# 7_3PCB_Sheet.net
KiCad netlist of a schematic drawn in EasyEDA
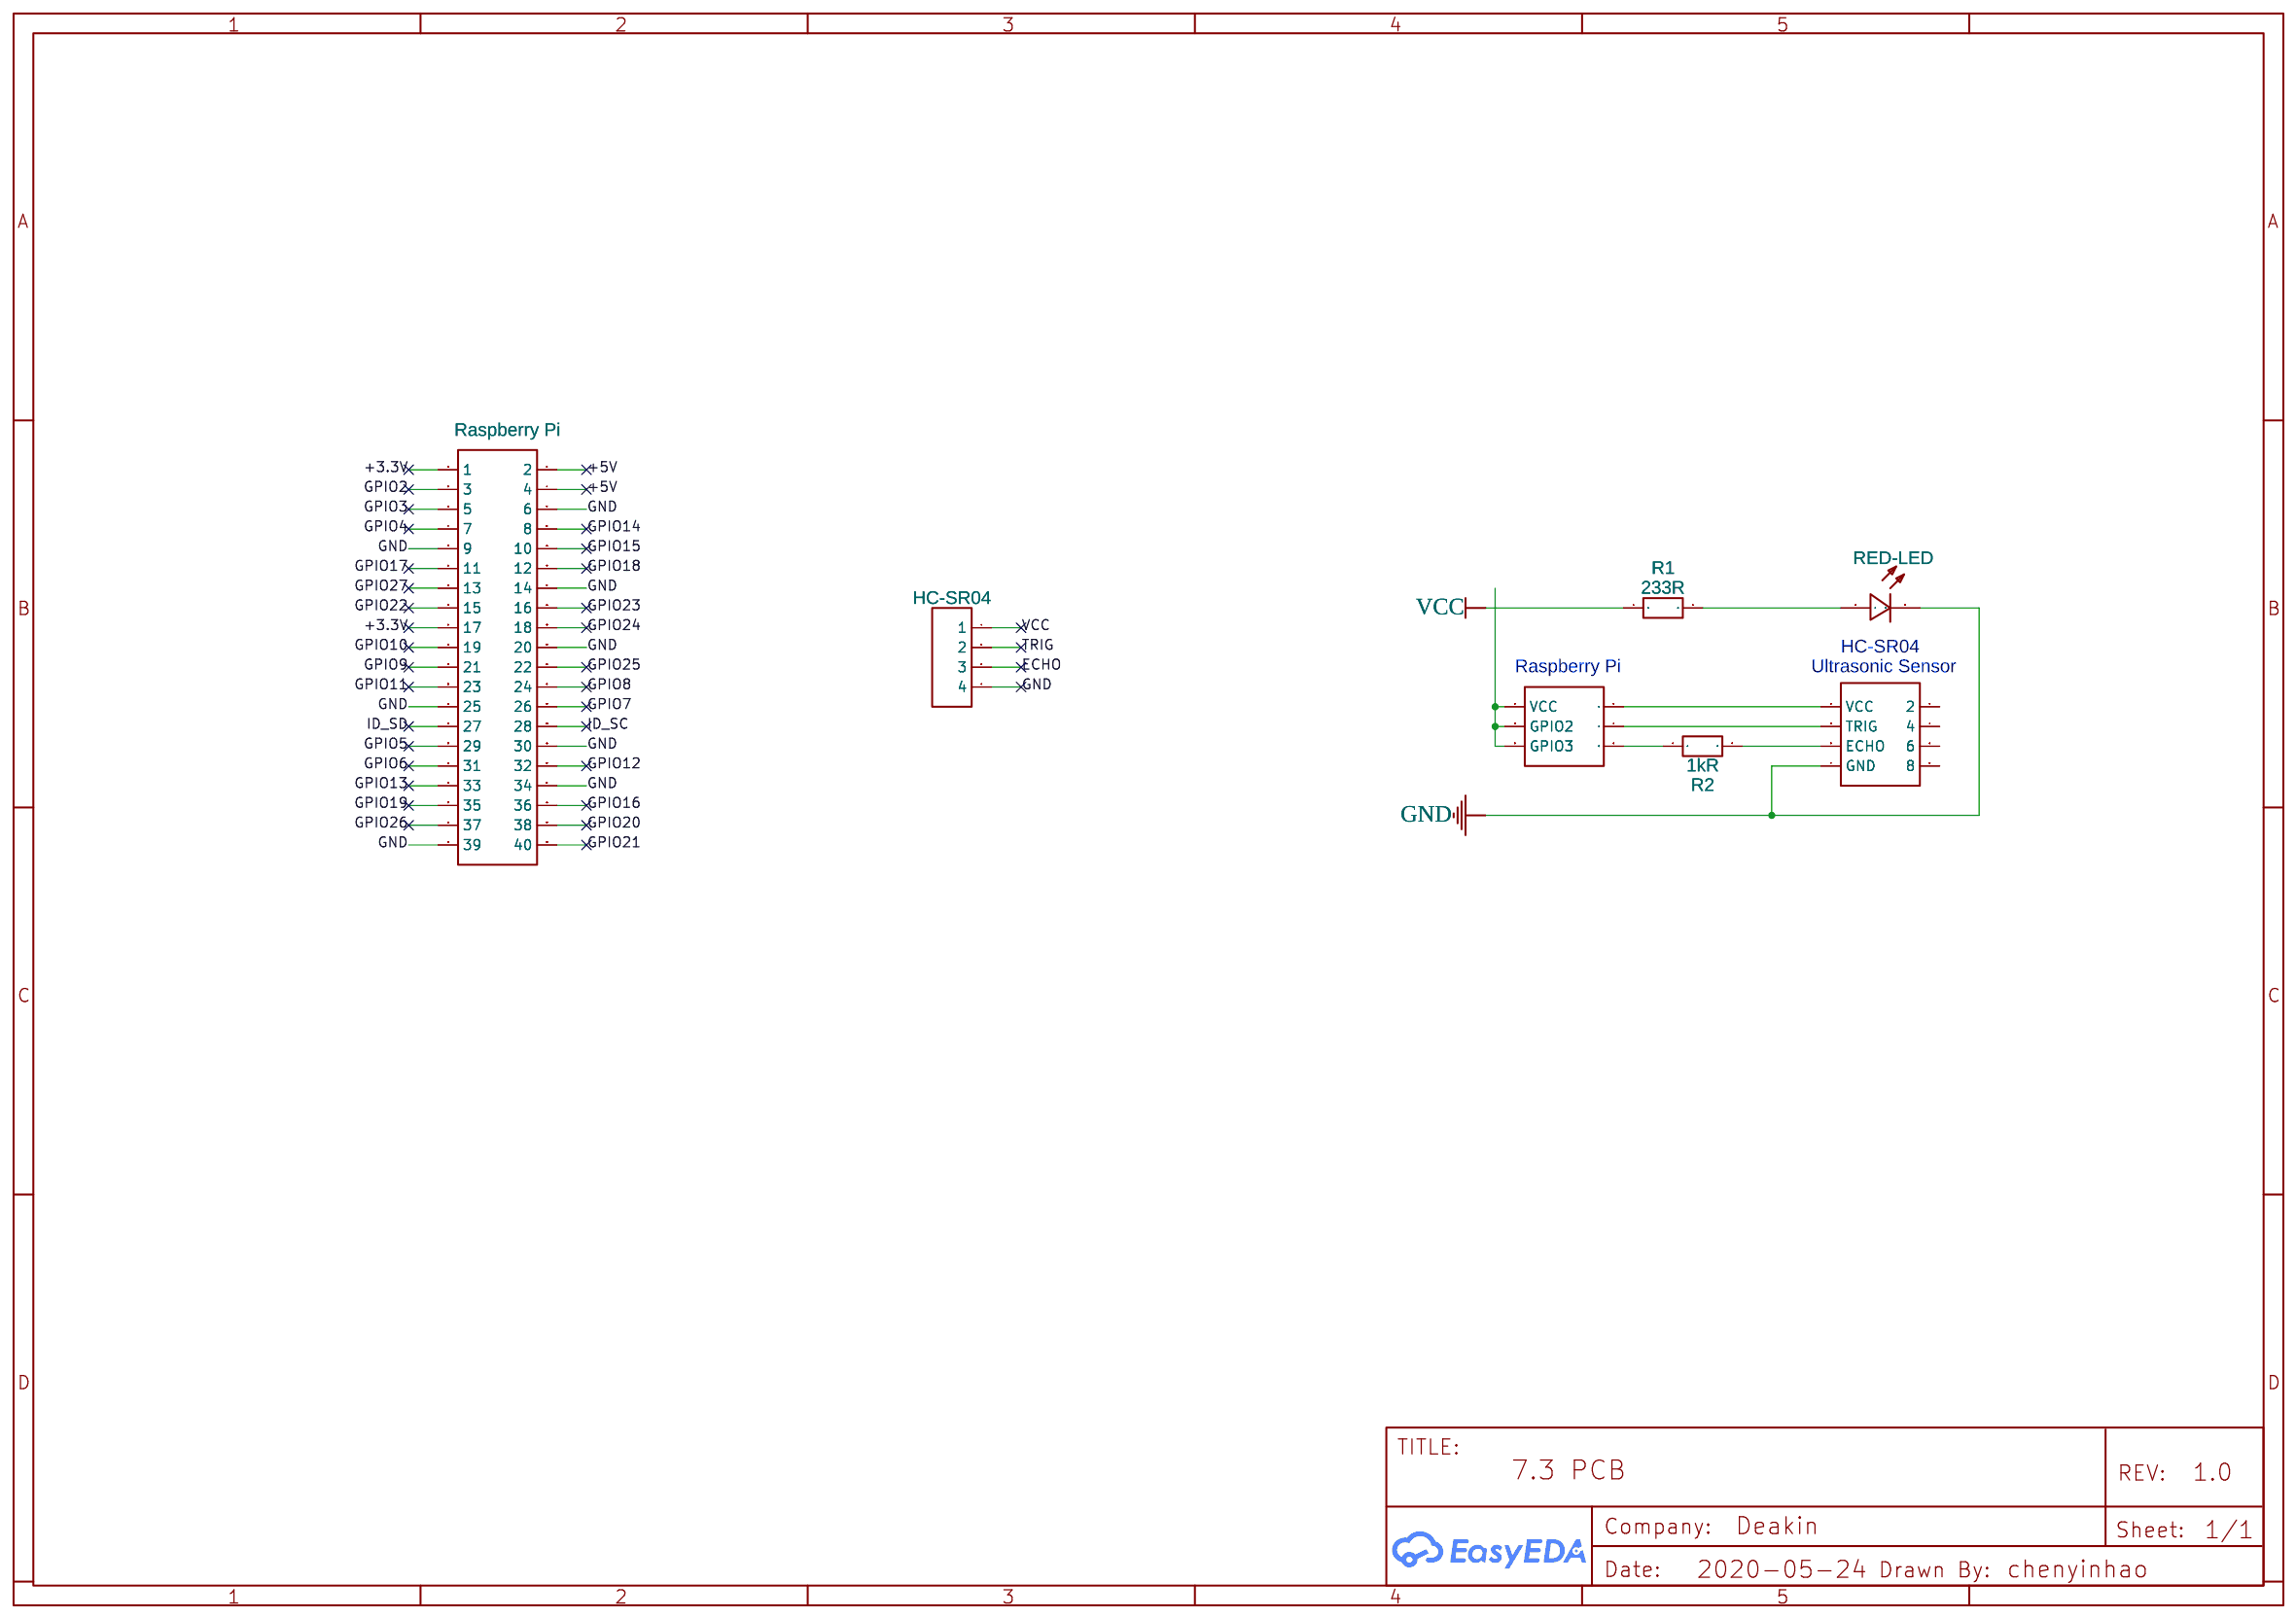
[diagram p0: schematic sheet]

(export (version "E")
  (design (tool "Eeschema 10.0.6"))
  (components
    (comp (ref "H1")
      (value "HC-SR04")
      (fields (field (name "BOM_Supplier Part") "C225501"))
      (libsource (lib "") (part "HDR-F-2.54_1x4"))
    )
    (comp (ref "J1")
      (value "HDR-M-2.54_2x4")
      (fields (field (name "BOM_Supplier Part") "C58363"))
      (libsource (lib "") (part "HDR-M-2.54_2x4"))
    )
    (comp (ref "P1")
      (value "Raspberry Pi")
      (fields (field (name "BOM_Supplier Part") "C50982"))
      (libsource (lib "") (part "HDR-F-2.54_2x20"))
    )
    (comp (ref "P2")
      (value "HDR-IDC-2.54-2X3P")
      (fields
        (field (name "BOM_Manufacturer Part") "2X3 2.54mm IDC Box")
        (field (name "BOM_Supplier Part") "C11214")
      )
      (libsource (lib "") (part "HDR-IDC-2.54-2X3P"))
    )
    (comp (ref "R1") (value "233R") (libsource (lib "") (part "R_0201_EU")))
    (comp (ref "R2") (value "1kR") (libsource (lib "") (part "R_0201_EU")))
    (comp (ref "RED-LED")
      (value "TJ-L3FYTGHRMBCLFLC4R-A5")
      (fields (field (name "BOM_Supplier Part") "C330773"))
      (libsource (lib "") (part "TJ-L3FYTGHRMBCLFLC4R-A5"))
    )
  )
  (nets
    (net (code "1") (name "/+3.3V") (class "Default")
      (node (ref "P1") (pin "1") (pinfunction "1_1") (pintype "input"))
      (node (ref "P1") (pin "17") (pinfunction "17_17") (pintype "input"))
    )
    (net (code "2") (name "/+5V") (class "Default")
      (node (ref "P1") (pin "2") (pinfunction "2_2") (pintype "input"))
      (node (ref "P1") (pin "4") (pinfunction "4_4") (pintype "input"))
    )
    (net (code "3") (name "/ECHO") (class "Default")
      (node (ref "H1") (pin "2") (pinfunction "3_2") (pintype "unspecified+no_connect"))
    )
    (net (code "4") (name "/GPIO2") (class "Default")
      (node (ref "P1") (pin "3") (pinfunction "3_3") (pintype "input+no_connect"))
    )
    (net (code "5") (name "/GPIO3") (class "Default")
      (node (ref "P1") (pin "5") (pinfunction "5_5") (pintype "input+no_connect"))
    )
    (net (code "6") (name "/GPIO4") (class "Default")
      (node (ref "P1") (pin "7") (pinfunction "7_7") (pintype "input+no_connect"))
    )
    (net (code "7") (name "/GPIO5") (class "Default")
      (node (ref "P1") (pin "29") (pinfunction "29_29") (pintype "input+no_connect"))
    )
    (net (code "8") (name "/GPIO6") (class "Default")
      (node (ref "P1") (pin "31") (pinfunction "31_31") (pintype "input+no_connect"))
    )
    (net (code "9") (name "/GPIO7") (class "Default")
      (node (ref "P1") (pin "26") (pinfunction "26_26") (pintype "input+no_connect"))
    )
    (net (code "10") (name "/GPIO8") (class "Default")
      (node (ref "P1") (pin "24") (pinfunction "24_24") (pintype "input+no_connect"))
    )
    (net (code "11") (name "/GPIO9") (class "Default")
      (node (ref "P1") (pin "21") (pinfunction "21_21") (pintype "input+no_connect"))
    )
    (net (code "12") (name "/GPIO10") (class "Default")
      (node (ref "P1") (pin "19") (pinfunction "19_19") (pintype "input+no_connect"))
    )
    (net (code "13") (name "/GPIO11") (class "Default")
      (node (ref "P1") (pin "23") (pinfunction "23_23") (pintype "input+no_connect"))
    )
    (net (code "14") (name "/GPIO12") (class "Default")
      (node (ref "P1") (pin "32") (pinfunction "32_32") (pintype "input+no_connect"))
    )
    (net (code "15") (name "/GPIO13") (class "Default")
      (node (ref "P1") (pin "33") (pinfunction "33_33") (pintype "input+no_connect"))
    )
    (net (code "16") (name "/GPIO14") (class "Default")
      (node (ref "P1") (pin "8") (pinfunction "8_8") (pintype "input+no_connect"))
    )
    (net (code "17") (name "/GPIO15") (class "Default")
      (node (ref "P1") (pin "10") (pinfunction "10_10") (pintype "input+no_connect"))
    )
    (net (code "18") (name "/GPIO16") (class "Default")
      (node (ref "P1") (pin "36") (pinfunction "36_36") (pintype "input+no_connect"))
    )
    (net (code "19") (name "/GPIO17") (class "Default")
      (node (ref "P1") (pin "11") (pinfunction "11_11") (pintype "input+no_connect"))
    )
    (net (code "20") (name "/GPIO18") (class "Default")
      (node (ref "P1") (pin "12") (pinfunction "12_12") (pintype "input+no_connect"))
    )
    (net (code "21") (name "/GPIO19") (class "Default")
      (node (ref "P1") (pin "35") (pinfunction "35_35") (pintype "input+no_connect"))
    )
    (net (code "22") (name "/GPIO20") (class "Default")
      (node (ref "P1") (pin "38") (pinfunction "38_38") (pintype "input+no_connect"))
    )
    (net (code "23") (name "/GPIO21") (class "Default")
      (node (ref "P1") (pin "40") (pinfunction "40_40") (pintype "input+no_connect"))
    )
    (net (code "24") (name "/GPIO22") (class "Default")
      (node (ref "P1") (pin "15") (pinfunction "15_15") (pintype "input+no_connect"))
    )
    (net (code "25") (name "/GPIO23") (class "Default")
      (node (ref "P1") (pin "16") (pinfunction "16_16") (pintype "input+no_connect"))
    )
    (net (code "26") (name "/GPIO24") (class "Default")
      (node (ref "P1") (pin "18") (pinfunction "18_18") (pintype "input+no_connect"))
    )
    (net (code "27") (name "/GPIO25") (class "Default")
      (node (ref "P1") (pin "22") (pinfunction "22_22") (pintype "input+no_connect"))
    )
    (net (code "28") (name "/GPIO26") (class "Default")
      (node (ref "P1") (pin "37") (pinfunction "37_37") (pintype "input+no_connect"))
    )
    (net (code "29") (name "/GPIO27") (class "Default")
      (node (ref "P1") (pin "13") (pinfunction "13_13") (pintype "input+no_connect"))
    )
    (net (code "30") (name "/ID_SC") (class "Default")
      (node (ref "P1") (pin "28") (pinfunction "28_28") (pintype "input+no_connect"))
    )
    (net (code "31") (name "/ID_SD") (class "Default")
      (node (ref "P1") (pin "27") (pinfunction "27_27") (pintype "input+no_connect"))
    )
    (net (code "32") (name "/TRIG") (class "Default")
      (node (ref "H1") (pin "3") (pinfunction "2_3") (pintype "unspecified+no_connect"))
    )
    (net (code "33") (name "GND") (class "Default")
      (node (ref "H1") (pin "1") (pinfunction "4_1") (pintype "unspecified"))
      (node (ref "J1") (pin "7") (pinfunction "GND_7") (pintype "unspecified"))
      (node (ref "P1") (pin "14") (pinfunction "14_14") (pintype "input"))
      (node (ref "P1") (pin "20") (pinfunction "20_20") (pintype "input"))
      (node (ref "P1") (pin "25") (pinfunction "25_25") (pintype "input"))
      (node (ref "P1") (pin "30") (pinfunction "30_30") (pintype "input"))
      (node (ref "P1") (pin "34") (pinfunction "34_34") (pintype "input"))
      (node (ref "P1") (pin "39") (pinfunction "39_39") (pintype "input"))
      (node (ref "P1") (pin "6") (pinfunction "6_6") (pintype "input"))
      (node (ref "P1") (pin "9") (pinfunction "9_9") (pintype "input"))
      (node (ref "RED-LED") (pin "2") (pinfunction "2_2") (pintype "unspecified"))
    )
    (net (code "34") (name "Net-(J1-ECHO)") (class "Default")
      (node (ref "J1") (pin "5") (pinfunction "ECHO_5") (pintype "unspecified"))
      (node (ref "R2") (pin "2") (pinfunction "2_2") (pintype "unspecified"))
    )
    (net (code "35") (name "Net-(J1-TRIG)") (class "Default")
      (node (ref "J1") (pin "3") (pinfunction "TRIG_3") (pintype "unspecified"))
      (node (ref "P2") (pin "4") (pinfunction "4_4") (pintype "unspecified"))
    )
    (net (code "36") (name "Net-(J1-VCC)") (class "Default")
      (node (ref "J1") (pin "1") (pinfunction "VCC_1") (pintype "unspecified"))
      (node (ref "P2") (pin "2") (pinfunction "2_2") (pintype "unspecified"))
    )
    (net (code "37") (name "Net-(P2-GPIO2)") (class "Default")
      (node (ref "P2") (pin "1") (pinfunction "VCC_1") (pintype "unspecified"))
      (node (ref "P2") (pin "3") (pinfunction "GPIO2_3") (pintype "unspecified"))
      (node (ref "P2") (pin "5") (pinfunction "GPIO3_5") (pintype "unspecified"))
    )
    (net (code "38") (name "Net-(P2-Pad6)") (class "Default")
      (node (ref "P2") (pin "6") (pinfunction "6_6") (pintype "unspecified"))
      (node (ref "R2") (pin "1") (pinfunction "1_1") (pintype "unspecified"))
    )
    (net (code "39") (name "Net-(R1-Pad2)") (class "Default")
      (node (ref "R1") (pin "2") (pinfunction "2_2") (pintype "unspecified"))
      (node (ref "RED-LED") (pin "1") (pinfunction "1_1") (pintype "unspecified"))
    )
    (net (code "40") (name "VCC") (class "Default")
      (node (ref "H1") (pin "4") (pinfunction "1_4") (pintype "unspecified"))
      (node (ref "R1") (pin "1") (pinfunction "1_1") (pintype "unspecified"))
    )
    (net (code "41") (name "unconnected-(J1-Pad2)") (class "Default")
      (node (ref "J1") (pin "2") (pinfunction "2_2") (pintype "unspecified"))
    )
    (net (code "42") (name "unconnected-(J1-Pad4)") (class "Default")
      (node (ref "J1") (pin "4") (pinfunction "4_4") (pintype "unspecified"))
    )
    (net (code "43") (name "unconnected-(J1-Pad6)") (class "Default")
      (node (ref "J1") (pin "6") (pinfunction "6_6") (pintype "unspecified"))
    )
    (net (code "44") (name "unconnected-(J1-Pad8)") (class "Default")
      (node (ref "J1") (pin "8") (pinfunction "8_8") (pintype "unspecified"))
    )
  )
)
